# nixie_clock.net
KiCad netlist of a schematic drawn in EAGLE
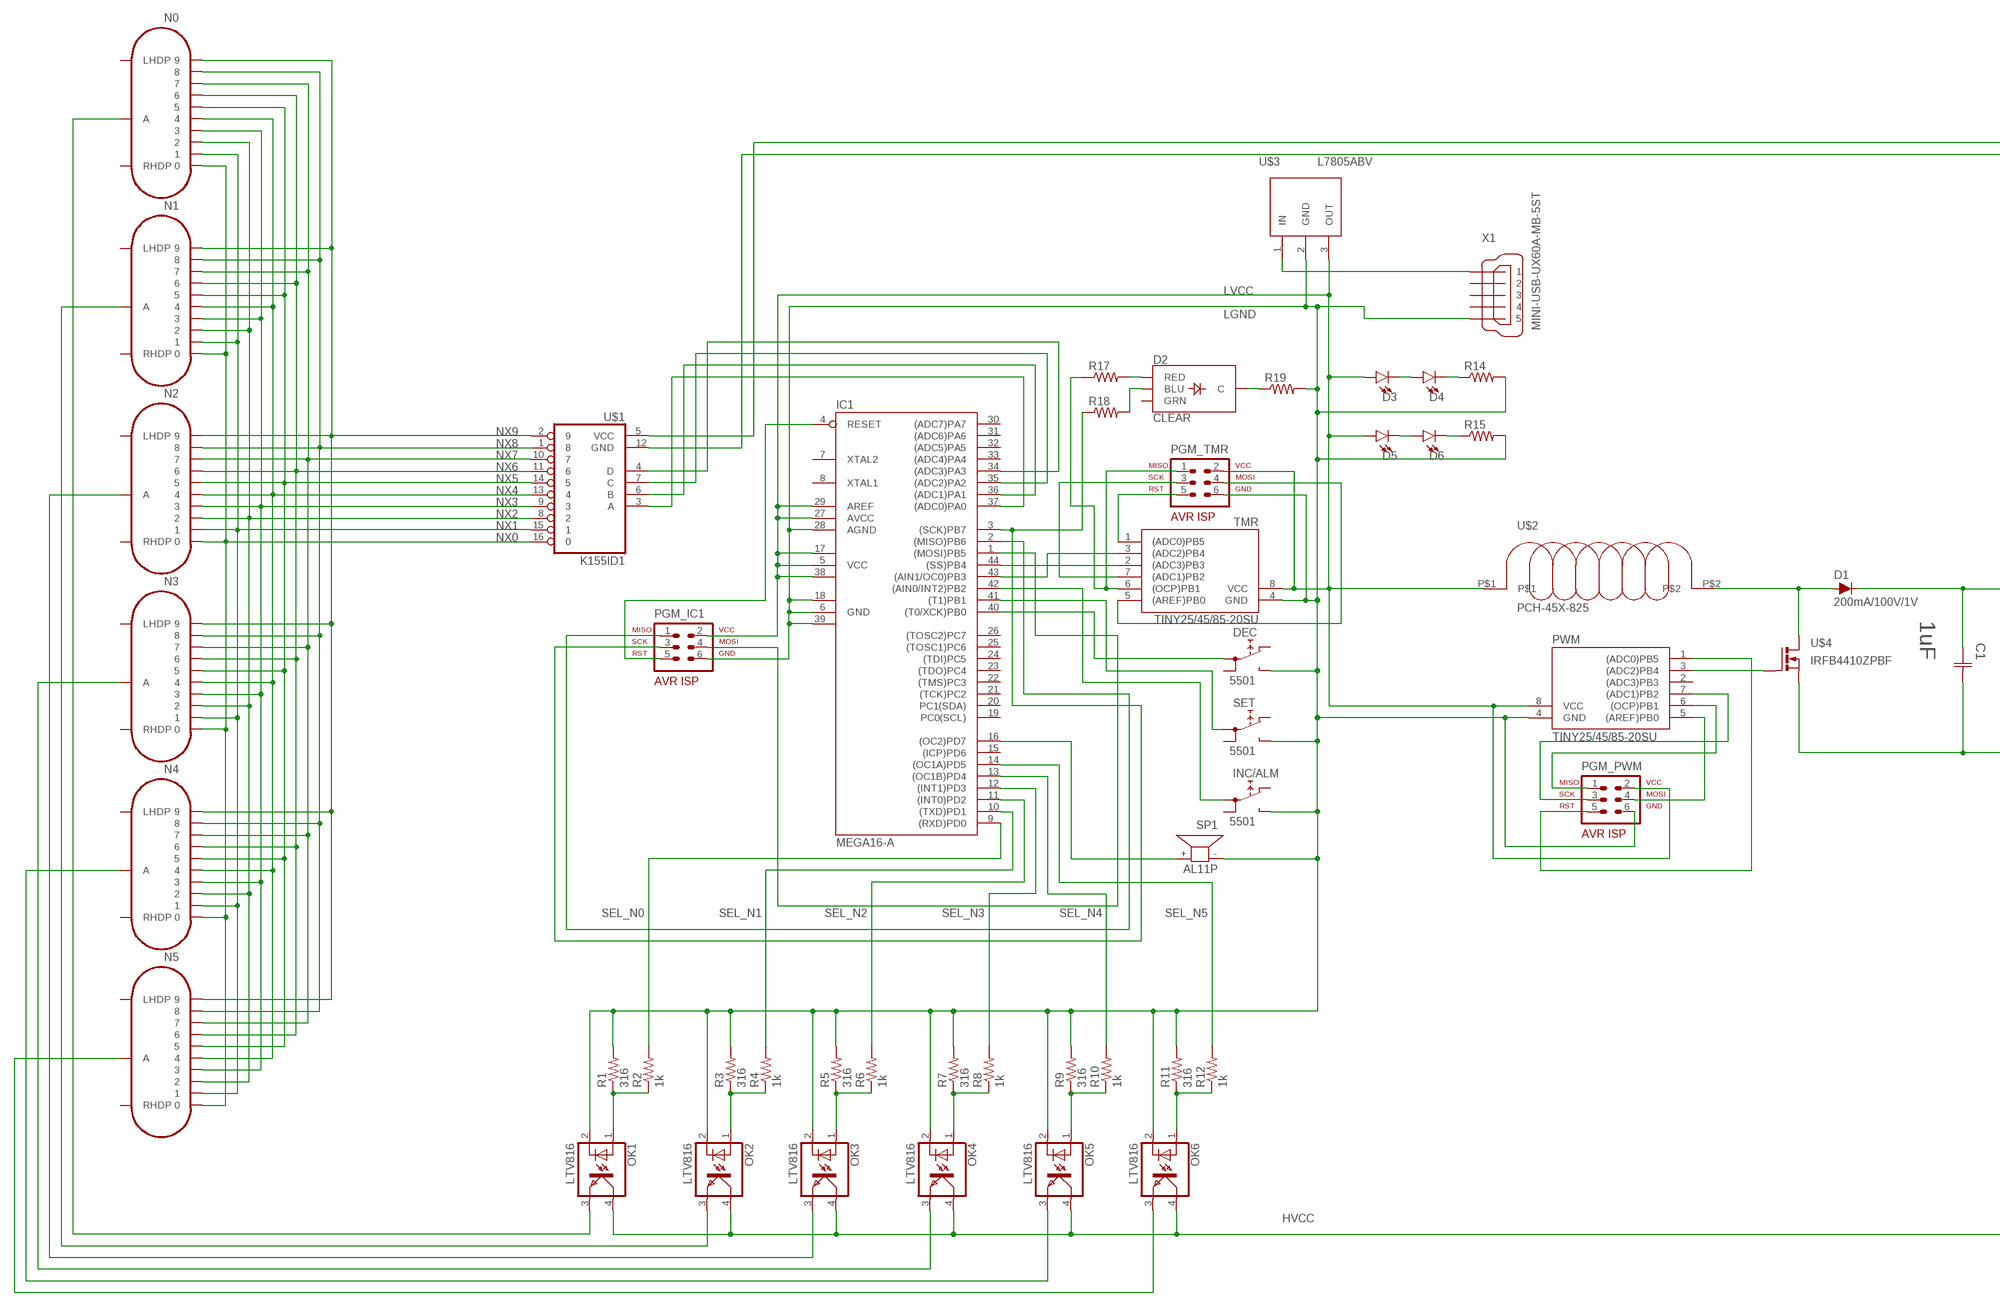
[diagram p0: schematic, sheet 1, part 1 of 2]
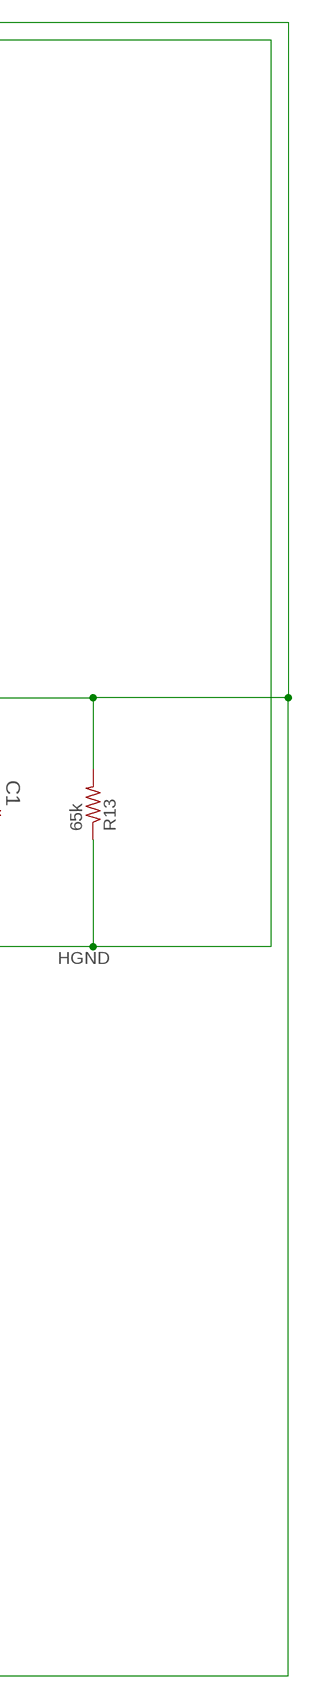
[diagram p1: schematic, sheet 1, part 2 of 2]

(export (version "E")
  (design (tool "Eeschema 10.0.6"))
  (components
    (comp (ref "C1")
      (value "1uF")
      (footprint "eagle-import:CAPC3225X170N")
      (fields (field (name "MPN") "C1210C105K5RACTU") (field (name "TOLERANCE") "±10%"))
      (libsource (lib "eagle-import") (part "C1210C105K5RACTU"))
    )
    (comp (ref "D1")
      (value "200mA/100V/1V")
      (footprint "eagle-import:DIODE-1N4148")
      (libsource (lib "eagle-import") (part "DIODE-1N4148"))
    )
    (comp (ref "D2")
      (value "CLEAR")
      (footprint "eagle-import:LED-RGB-THRU")
      (libsource (lib "eagle-import") (part "LED-RGB-CCCLEAR"))
    )
    (comp (ref "D3")
      (value "LED5MM")
      (footprint "eagle-import:LED_5MM")
      (libsource (lib "eagle-import") (part "LED5MM"))
    )
    (comp (ref "D4")
      (value "LED5MM")
      (footprint "eagle-import:LED_5MM")
      (libsource (lib "eagle-import") (part "LED5MM"))
    )
    (comp (ref "D5")
      (value "LED5MM")
      (footprint "eagle-import:LED_5MM")
      (libsource (lib "eagle-import") (part "LED5MM"))
    )
    (comp (ref "D6")
      (value "LED5MM")
      (footprint "eagle-import:LED_5MM")
      (libsource (lib "eagle-import") (part "LED5MM"))
    )
    (comp (ref "DEC")
      (value "5501")
      (footprint "eagle-import:5501")
      (libsource (lib "eagle-import") (part "55?01"))
    )
    (comp (ref "IC1")
      (value "MEGA16-A")
      (footprint "eagle-import:TQFP44")
      (libsource (lib "eagle-import") (part "MEGA16-A"))
    )
    (comp (ref "INC/ALM")
      (value "5501")
      (footprint "eagle-import:5501")
      (libsource (lib "eagle-import") (part "55?01"))
    )
    (comp (ref "N0")
      (value "IN-14")
      (footprint "eagle-import:IN-14")
      (libsource (lib "eagle-import") (part "IN-14"))
    )
    (comp (ref "N1")
      (value "IN-14")
      (footprint "eagle-import:IN-14")
      (libsource (lib "eagle-import") (part "IN-14"))
    )
    (comp (ref "N2")
      (value "IN-14")
      (footprint "eagle-import:IN-14")
      (libsource (lib "eagle-import") (part "IN-14"))
    )
    (comp (ref "N3")
      (value "IN-14")
      (footprint "eagle-import:IN-14")
      (libsource (lib "eagle-import") (part "IN-14"))
    )
    (comp (ref "N4")
      (value "IN-14")
      (footprint "eagle-import:IN-14")
      (libsource (lib "eagle-import") (part "IN-14"))
    )
    (comp (ref "N5")
      (value "IN-14")
      (footprint "eagle-import:IN-14")
      (libsource (lib "eagle-import") (part "IN-14"))
    )
    (comp (ref "OK1")
      (value "LTV816")
      (footprint "eagle-import:DIL04")
      (libsource (lib "eagle-import") (part "LTV816"))
    )
    (comp (ref "OK2")
      (value "LTV816")
      (footprint "eagle-import:DIL04")
      (libsource (lib "eagle-import") (part "LTV816"))
    )
    (comp (ref "OK3")
      (value "LTV816")
      (footprint "eagle-import:DIL04")
      (libsource (lib "eagle-import") (part "LTV816"))
    )
    (comp (ref "OK4")
      (value "LTV816")
      (footprint "eagle-import:DIL04")
      (libsource (lib "eagle-import") (part "LTV816"))
    )
    (comp (ref "OK5")
      (value "LTV816")
      (footprint "eagle-import:DIL04")
      (libsource (lib "eagle-import") (part "LTV816"))
    )
    (comp (ref "OK6")
      (value "LTV816")
      (footprint "eagle-import:DIL04")
      (libsource (lib "eagle-import") (part "LTV816"))
    )
    (comp (ref "PGM_IC1")
      (value "AVR-ISP-6HORZ")
      (footprint "eagle-import:AVR-ISP-6R")
      (libsource (lib "eagle-import") (part "AVR-ISP-6HORZ"))
    )
    (comp (ref "PGM_PWM")
      (value "AVR-ISP-6HORZ")
      (footprint "eagle-import:AVR-ISP-6R")
      (libsource (lib "eagle-import") (part "AVR-ISP-6HORZ"))
    )
    (comp (ref "PGM_TMR")
      (value "AVR-ISP-6HORZ")
      (footprint "eagle-import:AVR-ISP-6R")
      (libsource (lib "eagle-import") (part "AVR-ISP-6HORZ"))
    )
    (comp (ref "PWM")
      (value "TINY25/45/85-20SU")
      (footprint "eagle-import:SOIC8")
      (libsource (lib "eagle-import") (part "TINY25/45/85-20SU"))
    )
    (comp (ref "R1")
      (value "316")
      (footprint "eagle-import:M1206")
      (libsource (lib "eagle-import") (part "R-US_M1206"))
    )
    (comp (ref "R2")
      (value "1k")
      (footprint "eagle-import:M1206")
      (libsource (lib "eagle-import") (part "R-US_M1206"))
    )
    (comp (ref "R3")
      (value "316")
      (footprint "eagle-import:M1206")
      (libsource (lib "eagle-import") (part "R-US_M1206"))
    )
    (comp (ref "R4")
      (value "1k")
      (footprint "eagle-import:M1206")
      (libsource (lib "eagle-import") (part "R-US_M1206"))
    )
    (comp (ref "R5")
      (value "316")
      (footprint "eagle-import:M1206")
      (libsource (lib "eagle-import") (part "R-US_M1206"))
    )
    (comp (ref "R6")
      (value "1k")
      (footprint "eagle-import:M1206")
      (libsource (lib "eagle-import") (part "R-US_M1206"))
    )
    (comp (ref "R7")
      (value "316")
      (footprint "eagle-import:M1206")
      (libsource (lib "eagle-import") (part "R-US_M1206"))
    )
    (comp (ref "R8")
      (value "1k")
      (footprint "eagle-import:M1206")
      (libsource (lib "eagle-import") (part "R-US_M1206"))
    )
    (comp (ref "R9")
      (value "316")
      (footprint "eagle-import:M1206")
      (libsource (lib "eagle-import") (part "R-US_M1206"))
    )
    (comp (ref "R10")
      (value "1k")
      (footprint "eagle-import:M1206")
      (libsource (lib "eagle-import") (part "R-US_M1206"))
    )
    (comp (ref "R11")
      (value "316")
      (footprint "eagle-import:M1206")
      (libsource (lib "eagle-import") (part "R-US_M1206"))
    )
    (comp (ref "R12")
      (value "1k")
      (footprint "eagle-import:M1206")
      (libsource (lib "eagle-import") (part "R-US_M1206"))
    )
    (comp (ref "R13")
      (value "65k")
      (footprint "eagle-import:M1206")
      (libsource (lib "eagle-import") (part "R-US_M1206"))
    )
    (comp (ref "R14")
      (value "R-US_0204/7")
      (footprint "eagle-import:0204_7")
      (libsource (lib "eagle-import") (part "R-US_0204/7"))
    )
    (comp (ref "R15")
      (value "R-US_0204/7")
      (footprint "eagle-import:0204_7")
      (libsource (lib "eagle-import") (part "R-US_0204/7"))
    )
    (comp (ref "R17")
      (value "R-US_0204/7")
      (footprint "eagle-import:0204_7")
      (libsource (lib "eagle-import") (part "R-US_0204/7"))
    )
    (comp (ref "R18")
      (value "R-US_0204/7")
      (footprint "eagle-import:0204_7")
      (libsource (lib "eagle-import") (part "R-US_0204/7"))
    )
    (comp (ref "R19")
      (value "R-US_0204/7")
      (footprint "eagle-import:0204_7")
      (libsource (lib "eagle-import") (part "R-US_0204/7"))
    )
    (comp (ref "SET")
      (value "5501")
      (footprint "eagle-import:5501")
      (libsource (lib "eagle-import") (part "55?01"))
    )
    (comp (ref "SP1")
      (value "AL11P")
      (footprint "eagle-import:AL11P")
      (libsource (lib "eagle-import") (part "AL11P"))
    )
    (comp (ref "TMR")
      (value "TINY25/45/85-20SU")
      (footprint "eagle-import:SOIC8")
      (libsource (lib "eagle-import") (part "TINY25/45/85-20SU"))
    )
    (comp (ref "U$1")
      (value "K155ID1")
      (footprint "eagle-import:DIL16")
      (libsource (lib "eagle-import") (part "K155ID1"))
    )
    (comp (ref "U$2")
      (value "PCH-45X-825")
      (footprint "eagle-import:PCH-45X-825")
      (libsource (lib "eagle-import") (part "PCH-45X-825"))
    )
    (comp (ref "U$3")
      (value "L7805ABV")
      (footprint "eagle-import:TO220AB")
      (libsource (lib "eagle-import") (part "L7805ABV"))
    )
    (comp (ref "U$4")
      (value "IRFB4410ZPBF")
      (footprint "eagle-import:TO220AB")
      (fields (field (name "SPICEPREFIX") "U"))
      (libsource (lib "eagle-import") (part "IRFB4410ZPBF"))
    )
    (comp (ref "X1")
      (value "MINI-USB-UX60A-MB-5ST")
      (footprint "eagle-import:UX60A-MB-5ST")
      (libsource (lib "eagle-import") (part "MINI-USB-UX60A-MB-5ST"))
    )
  )
  (nets
    (net (code "1") (name "/HGND") (class "Default")
      (node (ref "C1") (pin "2") (pinfunction "C2_2") (pintype "passive"))
      (node (ref "R13") (pin "1") (pinfunction "1_1") (pintype "passive"))
      (node (ref "U$1") (pin "12") (pinfunction "GND_12") (pintype "bidirectional"))
      (node (ref "U$4") (pin "3") (pinfunction "SG1_3") (pintype "passive"))
    )
    (net (code "2") (name "/HVCC") (class "Default")
      (node (ref "C1") (pin "1") (pinfunction "C1_1") (pintype "passive"))
      (node (ref "D1") (pin "C") (pinfunction "C_C") (pintype "passive"))
      (node (ref "OK1") (pin "4") (pinfunction "COL_4") (pintype "passive"))
      (node (ref "OK2") (pin "4") (pinfunction "COL_4") (pintype "passive"))
      (node (ref "OK3") (pin "4") (pinfunction "COL_4") (pintype "passive"))
      (node (ref "OK4") (pin "4") (pinfunction "COL_4") (pintype "passive"))
      (node (ref "OK5") (pin "4") (pinfunction "COL_4") (pintype "passive"))
      (node (ref "OK6") (pin "4") (pinfunction "COL_4") (pintype "passive"))
      (node (ref "R13") (pin "2") (pinfunction "2_2") (pintype "passive"))
      (node (ref "U$1") (pin "5") (pinfunction "VCC_5") (pintype "bidirectional"))
    )
    (net (code "3") (name "/LGND") (class "Default")
      (node (ref "DEC") (pin "NO") (pinfunction "NO_NO") (pintype "passive"))
      (node (ref "IC1") (pin "18") (pinfunction "GND1_18") (pintype "power_in"))
      (node (ref "IC1") (pin "28") (pinfunction "AGND_28") (pintype "power_in"))
      (node (ref "IC1") (pin "39") (pinfunction "GND2_39") (pintype "power_in"))
      (node (ref "IC1") (pin "6") (pinfunction "GND_6") (pintype "power_in"))
      (node (ref "INC/ALM") (pin "NO") (pinfunction "NO_NO") (pintype "passive"))
      (node (ref "OK1") (pin "2") (pinfunction "C_2") (pintype "passive"))
      (node (ref "OK2") (pin "2") (pinfunction "C_2") (pintype "passive"))
      (node (ref "OK3") (pin "2") (pinfunction "C_2") (pintype "passive"))
      (node (ref "OK4") (pin "2") (pinfunction "C_2") (pintype "passive"))
      (node (ref "OK5") (pin "2") (pinfunction "C_2") (pintype "passive"))
      (node (ref "OK6") (pin "2") (pinfunction "C_2") (pintype "passive"))
      (node (ref "PGM_IC1") (pin "6") (pinfunction "6_6") (pintype "passive"))
      (node (ref "PGM_PWM") (pin "6") (pinfunction "6_6") (pintype "passive"))
      (node (ref "PGM_TMR") (pin "6") (pinfunction "6_6") (pintype "passive"))
      (node (ref "PWM") (pin "4") (pinfunction "GND_4") (pintype "power_in"))
      (node (ref "R1") (pin "2") (pinfunction "2_2") (pintype "passive"))
      (node (ref "R11") (pin "2") (pinfunction "2_2") (pintype "passive"))
      (node (ref "R14") (pin "2") (pinfunction "2_2") (pintype "passive"))
      (node (ref "R15") (pin "2") (pinfunction "2_2") (pintype "passive"))
      (node (ref "R19") (pin "2") (pinfunction "2_2") (pintype "passive"))
      (node (ref "R3") (pin "2") (pinfunction "2_2") (pintype "passive"))
      (node (ref "R5") (pin "2") (pinfunction "2_2") (pintype "passive"))
      (node (ref "R7") (pin "2") (pinfunction "2_2") (pintype "passive"))
      (node (ref "R9") (pin "2") (pinfunction "2_2") (pintype "passive"))
      (node (ref "SET") (pin "NO") (pinfunction "NO_NO") (pintype "passive"))
      (node (ref "SP1") (pin "-") (pinfunction "1_-") (pintype "passive"))
      (node (ref "TMR") (pin "4") (pinfunction "GND_4") (pintype "power_in"))
      (node (ref "U$3") (pin "2") (pinfunction "GND_2") (pintype "bidirectional"))
      (node (ref "X1") (pin "5") (pinfunction "5_5") (pintype "input"))
    )
    (net (code "4") (name "/LVCC") (class "Default")
      (node (ref "D3") (pin "A") (pinfunction "A_A") (pintype "passive"))
      (node (ref "D5") (pin "A") (pinfunction "A_A") (pintype "passive"))
      (node (ref "IC1") (pin "17") (pinfunction "VCC1_17") (pintype "power_in"))
      (node (ref "IC1") (pin "27") (pinfunction "AVCC_27") (pintype "power_in"))
      (node (ref "IC1") (pin "29") (pinfunction "AREF_29") (pintype "power_in"))
      (node (ref "IC1") (pin "38") (pinfunction "VCC2_38") (pintype "power_in"))
      (node (ref "IC1") (pin "5") (pinfunction "VCC_5") (pintype "power_in"))
      (node (ref "PGM_IC1") (pin "2") (pinfunction "2_2") (pintype "passive"))
      (node (ref "PGM_PWM") (pin "2") (pinfunction "2_2") (pintype "passive"))
      (node (ref "PGM_TMR") (pin "2") (pinfunction "2_2") (pintype "passive"))
      (node (ref "PWM") (pin "8") (pinfunction "VCC_8") (pintype "power_in"))
      (node (ref "TMR") (pin "8") (pinfunction "VCC_8") (pintype "power_in"))
      (node (ref "U$2") (pin "P$1") (pinfunction "P$1_P$1") (pintype "bidirectional"))
      (node (ref "U$3") (pin "3") (pinfunction "OUT_3") (pintype "bidirectional"))
    )
    (net (code "5") (name "/NX0") (class "Default")
      (node (ref "N0") (pin "0") (pinfunction "0_0") (pintype "bidirectional"))
      (node (ref "N1") (pin "0") (pinfunction "0_0") (pintype "bidirectional"))
      (node (ref "N2") (pin "0") (pinfunction "0_0") (pintype "bidirectional"))
      (node (ref "N3") (pin "0") (pinfunction "0_0") (pintype "bidirectional"))
      (node (ref "N4") (pin "0") (pinfunction "0_0") (pintype "bidirectional"))
      (node (ref "N5") (pin "0") (pinfunction "0_0") (pintype "bidirectional"))
      (node (ref "U$1") (pin "16") (pinfunction "0_16") (pintype "open_collector"))
    )
    (net (code "6") (name "/NX1") (class "Default")
      (node (ref "N0") (pin "1") (pinfunction "1_1") (pintype "bidirectional"))
      (node (ref "N1") (pin "1") (pinfunction "1_1") (pintype "bidirectional"))
      (node (ref "N2") (pin "1") (pinfunction "1_1") (pintype "bidirectional"))
      (node (ref "N3") (pin "1") (pinfunction "1_1") (pintype "bidirectional"))
      (node (ref "N4") (pin "1") (pinfunction "1_1") (pintype "bidirectional"))
      (node (ref "N5") (pin "1") (pinfunction "1_1") (pintype "bidirectional"))
      (node (ref "U$1") (pin "15") (pinfunction "1_15") (pintype "open_collector"))
    )
    (net (code "7") (name "/NX2") (class "Default")
      (node (ref "N0") (pin "2") (pinfunction "2_2") (pintype "bidirectional"))
      (node (ref "N1") (pin "2") (pinfunction "2_2") (pintype "bidirectional"))
      (node (ref "N2") (pin "2") (pinfunction "2_2") (pintype "bidirectional"))
      (node (ref "N3") (pin "2") (pinfunction "2_2") (pintype "bidirectional"))
      (node (ref "N4") (pin "2") (pinfunction "2_2") (pintype "bidirectional"))
      (node (ref "N5") (pin "2") (pinfunction "2_2") (pintype "bidirectional"))
      (node (ref "U$1") (pin "8") (pinfunction "2_8") (pintype "open_collector"))
    )
    (net (code "8") (name "/NX3") (class "Default")
      (node (ref "N0") (pin "3") (pinfunction "3_3") (pintype "bidirectional"))
      (node (ref "N1") (pin "3") (pinfunction "3_3") (pintype "bidirectional"))
      (node (ref "N2") (pin "3") (pinfunction "3_3") (pintype "bidirectional"))
      (node (ref "N3") (pin "3") (pinfunction "3_3") (pintype "bidirectional"))
      (node (ref "N4") (pin "3") (pinfunction "3_3") (pintype "bidirectional"))
      (node (ref "N5") (pin "3") (pinfunction "3_3") (pintype "bidirectional"))
      (node (ref "U$1") (pin "9") (pinfunction "3_9") (pintype "open_collector"))
    )
    (net (code "9") (name "/NX4") (class "Default")
      (node (ref "N0") (pin "4") (pinfunction "4_4") (pintype "bidirectional"))
      (node (ref "N1") (pin "4") (pinfunction "4_4") (pintype "bidirectional"))
      (node (ref "N2") (pin "4") (pinfunction "4_4") (pintype "bidirectional"))
      (node (ref "N3") (pin "4") (pinfunction "4_4") (pintype "bidirectional"))
      (node (ref "N4") (pin "4") (pinfunction "4_4") (pintype "bidirectional"))
      (node (ref "N5") (pin "4") (pinfunction "4_4") (pintype "bidirectional"))
      (node (ref "U$1") (pin "13") (pinfunction "4_13") (pintype "open_collector"))
    )
    (net (code "10") (name "/NX5") (class "Default")
      (node (ref "N0") (pin "5") (pinfunction "5_5") (pintype "bidirectional"))
      (node (ref "N1") (pin "5") (pinfunction "5_5") (pintype "bidirectional"))
      (node (ref "N2") (pin "5") (pinfunction "5_5") (pintype "bidirectional"))
      (node (ref "N3") (pin "5") (pinfunction "5_5") (pintype "bidirectional"))
      (node (ref "N4") (pin "5") (pinfunction "5_5") (pintype "bidirectional"))
      (node (ref "N5") (pin "5") (pinfunction "5_5") (pintype "bidirectional"))
      (node (ref "U$1") (pin "14") (pinfunction "5_14") (pintype "open_collector"))
    )
    (net (code "11") (name "/NX6") (class "Default")
      (node (ref "N0") (pin "6") (pinfunction "6_6") (pintype "bidirectional"))
      (node (ref "N1") (pin "6") (pinfunction "6_6") (pintype "bidirectional"))
      (node (ref "N2") (pin "6") (pinfunction "6_6") (pintype "bidirectional"))
      (node (ref "N3") (pin "6") (pinfunction "6_6") (pintype "bidirectional"))
      (node (ref "N4") (pin "6") (pinfunction "6_6") (pintype "bidirectional"))
      (node (ref "N5") (pin "6") (pinfunction "6_6") (pintype "bidirectional"))
      (node (ref "U$1") (pin "11") (pinfunction "6_11") (pintype "open_collector"))
    )
    (net (code "12") (name "/NX7") (class "Default")
      (node (ref "N0") (pin "7") (pinfunction "7_7") (pintype "bidirectional"))
      (node (ref "N1") (pin "7") (pinfunction "7_7") (pintype "bidirectional"))
      (node (ref "N2") (pin "7") (pinfunction "7_7") (pintype "bidirectional"))
      (node (ref "N3") (pin "7") (pinfunction "7_7") (pintype "bidirectional"))
      (node (ref "N4") (pin "7") (pinfunction "7_7") (pintype "bidirectional"))
      (node (ref "N5") (pin "7") (pinfunction "7_7") (pintype "bidirectional"))
      (node (ref "U$1") (pin "10") (pinfunction "7_10") (pintype "open_collector"))
    )
    (net (code "13") (name "/NX8") (class "Default")
      (node (ref "N0") (pin "8") (pinfunction "8_8") (pintype "bidirectional"))
      (node (ref "N1") (pin "8") (pinfunction "8_8") (pintype "bidirectional"))
      (node (ref "N2") (pin "8") (pinfunction "8_8") (pintype "bidirectional"))
      (node (ref "N3") (pin "8") (pinfunction "8_8") (pintype "bidirectional"))
      (node (ref "N4") (pin "8") (pinfunction "8_8") (pintype "bidirectional"))
      (node (ref "N5") (pin "8") (pinfunction "8_8") (pintype "bidirectional"))
      (node (ref "U$1") (pin "1") (pinfunction "8_1") (pintype "open_collector"))
    )
    (net (code "14") (name "/NX9") (class "Default")
      (node (ref "N0") (pin "9") (pinfunction "9_9") (pintype "bidirectional"))
      (node (ref "N1") (pin "9") (pinfunction "9_9") (pintype "bidirectional"))
      (node (ref "N2") (pin "9") (pinfunction "9_9") (pintype "bidirectional"))
      (node (ref "N3") (pin "9") (pinfunction "9_9") (pintype "bidirectional"))
      (node (ref "N4") (pin "9") (pinfunction "9_9") (pintype "bidirectional"))
      (node (ref "N5") (pin "9") (pinfunction "9_9") (pintype "bidirectional"))
      (node (ref "U$1") (pin "2") (pinfunction "9_2") (pintype "open_collector"))
    )
    (net (code "15") (name "/SEL_N0") (class "Default")
      (node (ref "IC1") (pin "9") (pinfunction "(RXD)PD0_9") (pintype "bidirectional"))
      (node (ref "R2") (pin "2") (pinfunction "2_2") (pintype "passive"))
    )
    (net (code "16") (name "/SEL_N1") (class "Default")
      (node (ref "IC1") (pin "10") (pinfunction "(TXD)PD1_10") (pintype "bidirectional"))
      (node (ref "R4") (pin "2") (pinfunction "2_2") (pintype "passive"))
    )
    (net (code "17") (name "/SEL_N2") (class "Default")
      (node (ref "IC1") (pin "11") (pinfunction "(INT0)PD2_11") (pintype "bidirectional"))
      (node (ref "R6") (pin "2") (pinfunction "2_2") (pintype "passive"))
    )
    (net (code "18") (name "/SEL_N3") (class "Default")
      (node (ref "IC1") (pin "12") (pinfunction "(INT1)PD3_12") (pintype "bidirectional"))
      (node (ref "R8") (pin "2") (pinfunction "2_2") (pintype "passive"))
    )
    (net (code "19") (name "/SEL_N4") (class "Default")
      (node (ref "IC1") (pin "13") (pinfunction "(OC1B)PD4_13") (pintype "bidirectional"))
      (node (ref "R10") (pin "2") (pinfunction "2_2") (pintype "passive"))
    )
    (net (code "20") (name "/SEL_N5") (class "Default")
      (node (ref "IC1") (pin "14") (pinfunction "(OC1A)PD5_14") (pintype "bidirectional"))
      (node (ref "R12") (pin "2") (pinfunction "2_2") (pintype "passive"))
    )
    (net (code "21") (name "Net-(D2-BLU)") (class "Default")
      (node (ref "D2") (pin "4") (pinfunction "BLU_4") (pintype "bidirectional"))
      (node (ref "R18") (pin "2") (pinfunction "2_2") (pintype "passive"))
    )
    (net (code "22") (name "Net-(D2-C)") (class "Default")
      (node (ref "D2") (pin "2") (pinfunction "C_2") (pintype "bidirectional"))
      (node (ref "R19") (pin "1") (pinfunction "1_1") (pintype "passive"))
    )
    (net (code "23") (name "Net-(D2-RED)") (class "Default")
      (node (ref "D2") (pin "1") (pinfunction "RED_1") (pintype "bidirectional"))
      (node (ref "R17") (pin "2") (pinfunction "2_2") (pintype "passive"))
    )
    (net (code "24") (name "Net-(D3-C)") (class "Default")
      (node (ref "D3") (pin "K") (pinfunction "C_K") (pintype "passive"))
      (node (ref "D4") (pin "A") (pinfunction "A_A") (pintype "passive"))
    )
    (net (code "25") (name "Net-(D4-C)") (class "Default")
      (node (ref "D4") (pin "K") (pinfunction "C_K") (pintype "passive"))
      (node (ref "R14") (pin "1") (pinfunction "1_1") (pintype "passive"))
    )
    (net (code "26") (name "Net-(D5-C)") (class "Default")
      (node (ref "D5") (pin "K") (pinfunction "C_K") (pintype "passive"))
      (node (ref "D6") (pin "A") (pinfunction "A_A") (pintype "passive"))
    )
    (net (code "27") (name "Net-(D6-C)") (class "Default")
      (node (ref "D6") (pin "K") (pinfunction "C_K") (pintype "passive"))
      (node (ref "R15") (pin "1") (pinfunction "1_1") (pintype "passive"))
    )
    (net (code "28") (name "Net-(IC1-(ADC0)PA0)") (class "Default")
      (node (ref "IC1") (pin "37") (pinfunction "(ADC0)PA0_37") (pintype "bidirectional"))
      (node (ref "U$1") (pin "3") (pinfunction "A_3") (pintype "input"))
    )
    (net (code "29") (name "Net-(IC1-(ADC1)PA1)") (class "Default")
      (node (ref "IC1") (pin "36") (pinfunction "(ADC1)PA1_36") (pintype "bidirectional"))
      (node (ref "U$1") (pin "6") (pinfunction "B_6") (pintype "input"))
    )
    (net (code "30") (name "Net-(IC1-(ADC2)PA2)") (class "Default")
      (node (ref "IC1") (pin "35") (pinfunction "(ADC2)PA2_35") (pintype "bidirectional"))
      (node (ref "U$1") (pin "7") (pinfunction "C_7") (pintype "input"))
    )
    (net (code "31") (name "Net-(IC1-(ADC3)PA3)") (class "Default")
      (node (ref "IC1") (pin "34") (pinfunction "(ADC3)PA3_34") (pintype "bidirectional"))
      (node (ref "U$1") (pin "4") (pinfunction "D_4") (pintype "input"))
    )
    (net (code "32") (name "Net-(IC1-(AIN0{slash}INT2)PB2)") (class "Default")
      (node (ref "IC1") (pin "42") (pinfunction "(AIN0/INT2)PB2_42") (pintype "bidirectional"))
      (node (ref "INC/ALM") (pin "1A") (pinfunction "1A_1A") (pintype "passive"))
    )
    (net (code "33") (name "Net-(IC1-(AIN1{slash}OC0)PB3)") (class "Default")
      (node (ref "IC1") (pin "43") (pinfunction "(AIN1/OC0)PB3_43") (pintype "bidirectional"))
      (node (ref "TMR") (pin "3") (pinfunction "(ADC2)PB4_3") (pintype "bidirectional"))
    )
    (net (code "34") (name "Net-(IC1-(MISO)PB6)") (class "Default")
      (node (ref "IC1") (pin "2") (pinfunction "(MISO)PB6_2") (pintype "bidirectional"))
      (node (ref "PGM_IC1") (pin "1") (pinfunction "1_1") (pintype "passive"))
    )
    (net (code "35") (name "Net-(IC1-(MOSI)PB5)") (class "Default")
      (node (ref "IC1") (pin "1") (pinfunction "(MOSI)PB5_1") (pintype "bidirectional"))
      (node (ref "PGM_IC1") (pin "4") (pinfunction "4_4") (pintype "passive"))
    )
    (net (code "36") (name "Net-(IC1-(OC2)PD7)") (class "Default")
      (node (ref "IC1") (pin "16") (pinfunction "(OC2)PD7_16") (pintype "bidirectional"))
      (node (ref "SP1") (pin "+") (pinfunction "2_+") (pintype "passive"))
    )
    (net (code "37") (name "Net-(IC1-(SCK)PB7)") (class "Default")
      (node (ref "IC1") (pin "3") (pinfunction "(SCK)PB7_3") (pintype "bidirectional"))
      (node (ref "PGM_IC1") (pin "3") (pinfunction "3_3") (pintype "passive"))
      (node (ref "R18") (pin "1") (pinfunction "1_1") (pintype "passive"))
    )
    (net (code "38") (name "Net-(IC1-(SS)PB4)") (class "Default")
      (node (ref "IC1") (pin "44") (pinfunction "(SS)PB4_44") (pintype "bidirectional"))
      (node (ref "TMR") (pin "2") (pinfunction "(ADC3)PB3_2") (pintype "bidirectional"))
    )
    (net (code "39") (name "Net-(IC1-(T0{slash}XCK)PB0)") (class "Default")
      (node (ref "DEC") (pin "1A") (pinfunction "1A_1A") (pintype "passive"))
      (node (ref "IC1") (pin "40") (pinfunction "(T0/XCK)PB0_40") (pintype "bidirectional"))
    )
    (net (code "40") (name "Net-(IC1-(T1)PB1)") (class "Default")
      (node (ref "IC1") (pin "41") (pinfunction "(T1)PB1_41") (pintype "bidirectional"))
      (node (ref "SET") (pin "1A") (pinfunction "1A_1A") (pintype "passive"))
    )
    (net (code "41") (name "Net-(IC1-RESET)") (class "Default")
      (node (ref "IC1") (pin "4") (pinfunction "RESET_4") (pintype "input"))
      (node (ref "PGM_IC1") (pin "5") (pinfunction "5_5") (pintype "passive"))
    )
    (net (code "42") (name "Net-(OK1-A)") (class "Default")
      (node (ref "OK1") (pin "1") (pinfunction "A_1") (pintype "passive"))
      (node (ref "R1") (pin "1") (pinfunction "1_1") (pintype "passive"))
      (node (ref "R2") (pin "1") (pinfunction "1_1") (pintype "passive"))
    )
    (net (code "43") (name "Net-(OK1-EMIT)") (class "Default")
      (node (ref "N0") (pin "A") (pinfunction "A_A") (pintype "bidirectional"))
      (node (ref "OK1") (pin "3") (pinfunction "EMIT_3") (pintype "passive"))
    )
    (net (code "44") (name "Net-(OK2-A)") (class "Default")
      (node (ref "OK2") (pin "1") (pinfunction "A_1") (pintype "passive"))
      (node (ref "R3") (pin "1") (pinfunction "1_1") (pintype "passive"))
      (node (ref "R4") (pin "1") (pinfunction "1_1") (pintype "passive"))
    )
    (net (code "45") (name "Net-(OK2-EMIT)") (class "Default")
      (node (ref "N1") (pin "A") (pinfunction "A_A") (pintype "bidirectional"))
      (node (ref "OK2") (pin "3") (pinfunction "EMIT_3") (pintype "passive"))
    )
    (net (code "46") (name "Net-(OK3-A)") (class "Default")
      (node (ref "OK3") (pin "1") (pinfunction "A_1") (pintype "passive"))
      (node (ref "R5") (pin "1") (pinfunction "1_1") (pintype "passive"))
      (node (ref "R6") (pin "1") (pinfunction "1_1") (pintype "passive"))
    )
    (net (code "47") (name "Net-(OK3-EMIT)") (class "Default")
      (node (ref "N2") (pin "A") (pinfunction "A_A") (pintype "bidirectional"))
      (node (ref "OK3") (pin "3") (pinfunction "EMIT_3") (pintype "passive"))
    )
    (net (code "48") (name "Net-(OK4-A)") (class "Default")
      (node (ref "OK4") (pin "1") (pinfunction "A_1") (pintype "passive"))
      (node (ref "R7") (pin "1") (pinfunction "1_1") (pintype "passive"))
      (node (ref "R8") (pin "1") (pinfunction "1_1") (pintype "passive"))
    )
    (net (code "49") (name "Net-(OK4-EMIT)") (class "Default")
      (node (ref "N3") (pin "A") (pinfunction "A_A") (pintype "bidirectional"))
      (node (ref "OK4") (pin "3") (pinfunction "EMIT_3") (pintype "passive"))
    )
    (net (code "50") (name "Net-(OK5-A)") (class "Default")
      (node (ref "OK5") (pin "1") (pinfunction "A_1") (pintype "passive"))
      (node (ref "R10") (pin "1") (pinfunction "1_1") (pintype "passive"))
      (node (ref "R9") (pin "1") (pinfunction "1_1") (pintype "passive"))
    )
    (net (code "51") (name "Net-(OK5-EMIT)") (class "Default")
      (node (ref "N4") (pin "A") (pinfunction "A_A") (pintype "bidirectional"))
      (node (ref "OK5") (pin "3") (pinfunction "EMIT_3") (pintype "passive"))
    )
    (net (code "52") (name "Net-(OK6-A)") (class "Default")
      (node (ref "OK6") (pin "1") (pinfunction "A_1") (pintype "passive"))
      (node (ref "R11") (pin "1") (pinfunction "1_1") (pintype "passive"))
      (node (ref "R12") (pin "1") (pinfunction "1_1") (pintype "passive"))
    )
    (net (code "53") (name "Net-(OK6-EMIT)") (class "Default")
      (node (ref "N5") (pin "A") (pinfunction "A_A") (pintype "bidirectional"))
      (node (ref "OK6") (pin "3") (pinfunction "EMIT_3") (pintype "passive"))
    )
    (net (code "54") (name "Net-(PWM-(ADC0)PB5)") (class "Default")
      (node (ref "PGM_PWM") (pin "5") (pinfunction "5_5") (pintype "passive"))
      (node (ref "PWM") (pin "1") (pinfunction "(ADC0)PB5_1") (pintype "bidirectional"))
    )
    (net (code "55") (name "Net-(PWM-(ADC1)PB2)") (class "Default")
      (node (ref "PGM_PWM") (pin "3") (pinfunction "3_3") (pintype "passive"))
      (node (ref "PWM") (pin "7") (pinfunction "(ADC1)PB2_7") (pintype "bidirectional"))
    )
    (net (code "56") (name "Net-(PWM-(ADC2)PB4)") (class "Default")
      (node (ref "PWM") (pin "3") (pinfunction "(ADC2)PB4_3") (pintype "bidirectional"))
      (node (ref "U$4") (pin "1") (pinfunction "G_1") (pintype "passive"))
    )
    (net (code "57") (name "Net-(PWM-(AREF)PB0)") (class "Default")
      (node (ref "PGM_PWM") (pin "4") (pinfunction "4_4") (pintype "passive"))
      (node (ref "PWM") (pin "5") (pinfunction "(AREF)PB0_5") (pintype "bidirectional"))
    )
    (net (code "58") (name "Net-(PWM-(OCP)PB1)") (class "Default")
      (node (ref "PGM_PWM") (pin "1") (pinfunction "1_1") (pintype "passive"))
      (node (ref "PWM") (pin "6") (pinfunction "(OCP)PB1_6") (pintype "bidirectional"))
    )
    (net (code "59") (name "Net-(TMR-(ADC0)PB5)") (class "Default")
      (node (ref "PGM_TMR") (pin "5") (pinfunction "5_5") (pintype "passive"))
      (node (ref "TMR") (pin "1") (pinfunction "(ADC0)PB5_1") (pintype "bidirectional"))
    )
    (net (code "60") (name "Net-(TMR-(ADC1)PB2)") (class "Default")
      (node (ref "PGM_TMR") (pin "3") (pinfunction "3_3") (pintype "passive"))
      (node (ref "TMR") (pin "7") (pinfunction "(ADC1)PB2_7") (pintype "bidirectional"))
    )
    (net (code "61") (name "Net-(TMR-(AREF)PB0)") (class "Default")
      (node (ref "PGM_TMR") (pin "4") (pinfunction "4_4") (pintype "passive"))
      (node (ref "TMR") (pin "5") (pinfunction "(AREF)PB0_5") (pintype "bidirectional"))
    )
    (net (code "62") (name "Net-(TMR-(OCP)PB1)") (class "Default")
      (node (ref "PGM_TMR") (pin "1") (pinfunction "1_1") (pintype "passive"))
      (node (ref "R17") (pin "1") (pinfunction "1_1") (pintype "passive"))
      (node (ref "TMR") (pin "6") (pinfunction "(OCP)PB1_6") (pintype "bidirectional"))
    )
    (net (code "63") (name "Net-(U$3-IN)") (class "Default")
      (node (ref "U$3") (pin "1") (pinfunction "IN_1") (pintype "bidirectional"))
      (node (ref "X1") (pin "1") (pinfunction "1_1") (pintype "input"))
    )
    (net (code "64") (name "Net-(U$4-D)") (class "Default")
      (node (ref "D1") (pin "A") (pinfunction "A_A") (pintype "passive"))
      (node (ref "U$2") (pin "P$2") (pinfunction "P$2_P$2") (pintype "bidirectional"))
      (node (ref "U$4") (pin "2") (pinfunction "D_2") (pintype "passive"))
    )
    (net (code "65") (name "unconnected-(D2-GRN-Pad3)") (class "Default")
      (node (ref "D2") (pin "3") (pinfunction "GRN_3") (pintype "bidirectional"))
    )
    (net (code "66") (name "unconnected-(DEC-Pad1B)") (class "Default")
      (node (ref "DEC") (pin "1B") (pinfunction "1B_1B") (pintype "passive"))
    )
    (net (code "67") (name "unconnected-(DEC-PadNC)") (class "Default")
      (node (ref "DEC") (pin "NC") (pinfunction "NC_NC") (pintype "passive"))
    )
    (net (code "68") (name "unconnected-(IC1-(ADC4)PA4-Pad33)") (class "Default")
      (node (ref "IC1") (pin "33") (pinfunction "(ADC4)PA4_33") (pintype "bidirectional"))
    )
    (net (code "69") (name "unconnected-(IC1-(ADC5)PA5-Pad32)") (class "Default")
      (node (ref "IC1") (pin "32") (pinfunction "(ADC5)PA5_32") (pintype "bidirectional"))
    )
    (net (code "70") (name "unconnected-(IC1-(ADC6)PA6-Pad31)") (class "Default")
      (node (ref "IC1") (pin "31") (pinfunction "(ADC6)PA6_31") (pintype "bidirectional"))
    )
    (net (code "71") (name "unconnected-(IC1-(ADC7)PA7-Pad30)") (class "Default")
      (node (ref "IC1") (pin "30") (pinfunction "(ADC7)PA7_30") (pintype "bidirectional"))
    )
    (net (code "72") (name "unconnected-(IC1-(ICP)PD6-Pad15)") (class "Default")
      (node (ref "IC1") (pin "15") (pinfunction "(ICP)PD6_15") (pintype "bidirectional"))
    )
    (net (code "73") (name "unconnected-(IC1-(TCK)PC2-Pad21)") (class "Default")
      (node (ref "IC1") (pin "21") (pinfunction "(TCK)PC2_21") (pintype "bidirectional"))
    )
    (net (code "74") (name "unconnected-(IC1-(TDI)PC5-Pad24)") (class "Default")
      (node (ref "IC1") (pin "24") (pinfunction "(TDI)PC5_24") (pintype "bidirectional"))
    )
    (net (code "75") (name "unconnected-(IC1-(TDO)PC4-Pad23)") (class "Default")
      (node (ref "IC1") (pin "23") (pinfunction "(TDO)PC4_23") (pintype "bidirectional"))
    )
    (net (code "76") (name "unconnected-(IC1-(TMS)PC3-Pad22)") (class "Default")
      (node (ref "IC1") (pin "22") (pinfunction "(TMS)PC3_22") (pintype "bidirectional"))
    )
    (net (code "77") (name "unconnected-(IC1-(TOSC1)PC6-Pad25)") (class "Default")
      (node (ref "IC1") (pin "25") (pinfunction "(TOSC1)PC6_25") (pintype "bidirectional"))
    )
    (net (code "78") (name "unconnected-(IC1-(TOSC2)PC7-Pad26)") (class "Default")
      (node (ref "IC1") (pin "26") (pinfunction "(TOSC2)PC7_26") (pintype "bidirectional"))
    )
    (net (code "79") (name "unconnected-(IC1-PC0(SCL)-Pad19)") (class "Default")
      (node (ref "IC1") (pin "19") (pinfunction "PC0(SCL)_19") (pintype "bidirectional"))
    )
    (net (code "80") (name "unconnected-(IC1-PC1(SDA)-Pad20)") (class "Default")
      (node (ref "IC1") (pin "20") (pinfunction "PC1(SDA)_20") (pintype "bidirectional"))
    )
    (net (code "81") (name "unconnected-(IC1-XTAL1-Pad8)") (class "Default")
      (node (ref "IC1") (pin "8") (pinfunction "XTAL1_8") (pintype "bidirectional"))
    )
    (net (code "82") (name "unconnected-(IC1-XTAL2-Pad7)") (class "Default")
      (node (ref "IC1") (pin "7") (pinfunction "XTAL2_7") (pintype "bidirectional"))
    )
    (net (code "83") (name "unconnected-(INC/ALM-Pad1B)") (class "Default")
      (node (ref "INC/ALM") (pin "1B") (pinfunction "1B_1B") (pintype "passive"))
    )
    (net (code "84") (name "unconnected-(INC/ALM-PadNC)") (class "Default")
      (node (ref "INC/ALM") (pin "NC") (pinfunction "NC_NC") (pintype "passive"))
    )
    (net (code "85") (name "unconnected-(N0-PadLHDP)") (class "Default")
      (node (ref "N0") (pin "LHDP") (pinfunction "LHDP_LHDP") (pintype "bidirectional"))
    )
    (net (code "86") (name "unconnected-(N0-PadRHDP)") (class "Default")
      (node (ref "N0") (pin "RHDP") (pinfunction "RHDP_RHDP") (pintype "bidirectional"))
    )
    (net (code "87") (name "unconnected-(N1-PadLHDP)") (class "Default")
      (node (ref "N1") (pin "LHDP") (pinfunction "LHDP_LHDP") (pintype "bidirectional"))
    )
    (net (code "88") (name "unconnected-(N1-PadRHDP)") (class "Default")
      (node (ref "N1") (pin "RHDP") (pinfunction "RHDP_RHDP") (pintype "bidirectional"))
    )
    (net (code "89") (name "unconnected-(N2-PadLHDP)") (class "Default")
      (node (ref "N2") (pin "LHDP") (pinfunction "LHDP_LHDP") (pintype "bidirectional"))
    )
    (net (code "90") (name "unconnected-(N2-PadRHDP)") (class "Default")
      (node (ref "N2") (pin "RHDP") (pinfunction "RHDP_RHDP") (pintype "bidirectional"))
    )
    (net (code "91") (name "unconnected-(N3-PadLHDP)") (class "Default")
      (node (ref "N3") (pin "LHDP") (pinfunction "LHDP_LHDP") (pintype "bidirectional"))
    )
    (net (code "92") (name "unconnected-(N3-PadRHDP)") (class "Default")
      (node (ref "N3") (pin "RHDP") (pinfunction "RHDP_RHDP") (pintype "bidirectional"))
    )
    (net (code "93") (name "unconnected-(N4-PadLHDP)") (class "Default")
      (node (ref "N4") (pin "LHDP") (pinfunction "LHDP_LHDP") (pintype "bidirectional"))
    )
    (net (code "94") (name "unconnected-(N4-PadRHDP)") (class "Default")
      (node (ref "N4") (pin "RHDP") (pinfunction "RHDP_RHDP") (pintype "bidirectional"))
    )
    (net (code "95") (name "unconnected-(N5-PadLHDP)") (class "Default")
      (node (ref "N5") (pin "LHDP") (pinfunction "LHDP_LHDP") (pintype "bidirectional"))
    )
    (net (code "96") (name "unconnected-(N5-PadRHDP)") (class "Default")
      (node (ref "N5") (pin "RHDP") (pinfunction "RHDP_RHDP") (pintype "bidirectional"))
    )
    (net (code "97") (name "unconnected-(PWM-(ADC3)PB3-Pad2)") (class "Default")
      (node (ref "PWM") (pin "2") (pinfunction "(ADC3)PB3_2") (pintype "bidirectional"))
    )
    (net (code "98") (name "unconnected-(SET-Pad1B)") (class "Default")
      (node (ref "SET") (pin "1B") (pinfunction "1B_1B") (pintype "passive"))
    )
    (net (code "99") (name "unconnected-(SET-PadNC)") (class "Default")
      (node (ref "SET") (pin "NC") (pinfunction "NC_NC") (pintype "passive"))
    )
    (net (code "100") (name "unconnected-(X1-Pad2)") (class "Default")
      (node (ref "X1") (pin "2") (pinfunction "2_2") (pintype "input"))
    )
    (net (code "101") (name "unconnected-(X1-Pad3)") (class "Default")
      (node (ref "X1") (pin "3") (pinfunction "3_3") (pintype "input"))
    )
    (net (code "102") (name "unconnected-(X1-Pad4)") (class "Default")
      (node (ref "X1") (pin "4") (pinfunction "4_4") (pintype "input"))
    )
  )
)
